# Low_Pass_Filter.net
KiCad netlist of a schematic drawn in Altium Designer
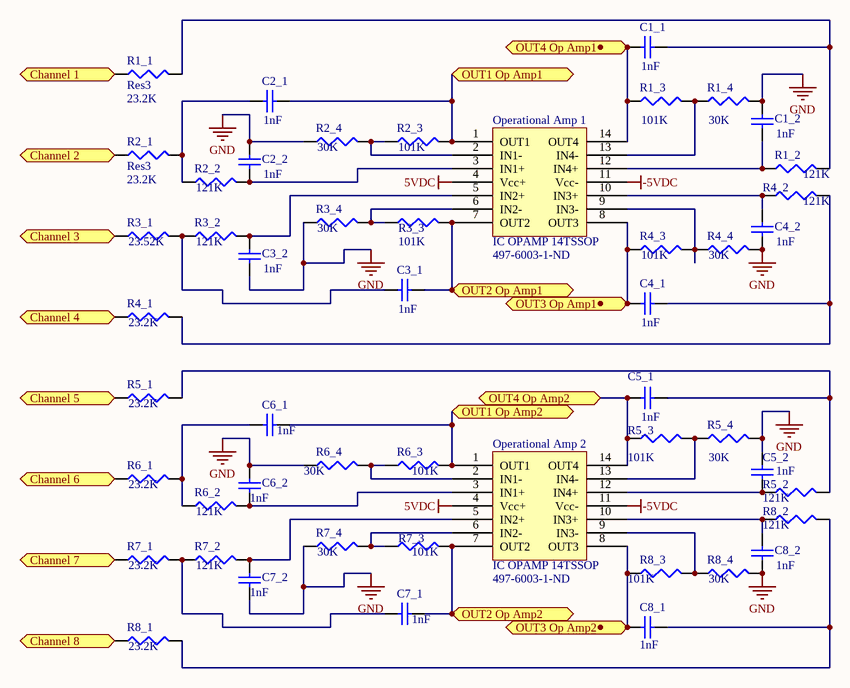
[diagram p0: Low Pass Filter.SchDoc]

(export (version "E")
  (design (tool "Eeschema 10.0.6"))
  (components
    (comp (ref "C1_1")
      (value "1nF")
      (footprint "C1206")
      (description "Capacitor (Semiconductor SIM Model)")
      (fields (field (name "Comment") "Cap Semi") (field (name "PUBLISHER") "Altium Limited"))
      (libsource (lib "Miscellaneous Devices") (part "Cap Semi"))
    )
    (comp (ref "C1_2")
      (value "1nF")
      (footprint "C1206")
      (description "Capacitor (Semiconductor SIM Model)")
      (fields (field (name "Comment") "Cap Semi") (field (name "PUBLISHER") "Altium Limited"))
      (libsource (lib "Miscellaneous Devices") (part "Cap Semi"))
    )
    (comp (ref "C2_1")
      (value "1nF")
      (footprint "C1206")
      (description "Capacitor (Semiconductor SIM Model)")
      (fields (field (name "Comment") "Cap Semi") (field (name "PUBLISHER") "Altium Limited"))
      (libsource (lib "Miscellaneous Devices") (part "Cap Semi"))
    )
    (comp (ref "C2_2")
      (value "1nF")
      (footprint "C1206")
      (description "Capacitor (Semiconductor SIM Model)")
      (fields (field (name "Comment") "Cap Semi") (field (name "PUBLISHER") "Altium Limited"))
      (libsource (lib "Miscellaneous Devices") (part "Cap Semi"))
    )
    (comp (ref "C3_1")
      (value "1nF")
      (footprint "C1206")
      (description "Capacitor (Semiconductor SIM Model)")
      (fields (field (name "Comment") "Cap Semi") (field (name "PUBLISHER") "Altium Limited"))
      (libsource (lib "Miscellaneous Devices") (part "Cap Semi"))
    )
    (comp (ref "C3_2")
      (value "1nF")
      (footprint "C1206")
      (description "Capacitor (Semiconductor SIM Model)")
      (fields (field (name "Comment") "Cap Semi") (field (name "PUBLISHER") "Altium Limited"))
      (libsource (lib "Miscellaneous Devices") (part "Cap Semi"))
    )
    (comp (ref "C4_1")
      (value "1nF")
      (footprint "C1206")
      (description "Capacitor (Semiconductor SIM Model)")
      (fields (field (name "Comment") "Cap Semi") (field (name "PUBLISHER") "Altium Limited"))
      (libsource (lib "Miscellaneous Devices") (part "Cap Semi"))
    )
    (comp (ref "C4_2")
      (value "1nF")
      (footprint "C1206")
      (description "Capacitor (Semiconductor SIM Model)")
      (fields (field (name "Comment") "Cap Semi") (field (name "PUBLISHER") "Altium Limited"))
      (libsource (lib "Miscellaneous Devices") (part "Cap Semi"))
    )
    (comp (ref "C5_1")
      (value "1nF")
      (footprint "C1206")
      (description "Capacitor (Semiconductor SIM Model)")
      (fields (field (name "Comment") "Cap Semi") (field (name "PUBLISHER") "Altium Limited"))
      (libsource (lib "Miscellaneous Devices") (part "Cap Semi"))
    )
    (comp (ref "C5_2")
      (value "1nF")
      (footprint "C1206")
      (description "Capacitor (Semiconductor SIM Model)")
      (fields (field (name "Comment") "Cap Semi") (field (name "PUBLISHER") "Altium Limited"))
      (libsource (lib "Miscellaneous Devices") (part "Cap Semi"))
    )
    (comp (ref "C6_1")
      (value "1nF")
      (footprint "C1206")
      (description "Capacitor (Semiconductor SIM Model)")
      (fields (field (name "Comment") "Cap Semi") (field (name "PUBLISHER") "Altium Limited"))
      (libsource (lib "Miscellaneous Devices") (part "Cap Semi"))
    )
    (comp (ref "C6_2")
      (value "1nF")
      (footprint "C1206")
      (description "Capacitor (Semiconductor SIM Model)")
      (fields (field (name "Comment") "Cap Semi") (field (name "PUBLISHER") "Altium Limited"))
      (libsource (lib "Miscellaneous Devices") (part "Cap Semi"))
    )
    (comp (ref "C7_1")
      (value "1nF")
      (footprint "C1206")
      (description "Capacitor (Semiconductor SIM Model)")
      (fields (field (name "Comment") "Cap Semi") (field (name "PUBLISHER") "Altium Limited"))
      (libsource (lib "Miscellaneous Devices") (part "Cap Semi"))
    )
    (comp (ref "C7_2")
      (value "1nF")
      (footprint "C1206")
      (description "Capacitor (Semiconductor SIM Model)")
      (fields (field (name "Comment") "Cap Semi") (field (name "PUBLISHER") "Altium Limited"))
      (libsource (lib "Miscellaneous Devices") (part "Cap Semi"))
    )
    (comp (ref "C8_1")
      (value "1nF")
      (footprint "C1206")
      (description "Capacitor (Semiconductor SIM Model)")
      (fields (field (name "Comment") "Cap Semi") (field (name "PUBLISHER") "Altium Limited"))
      (libsource (lib "Miscellaneous Devices") (part "Cap Semi"))
    )
    (comp (ref "C8_2")
      (value "1nF")
      (footprint "C1206")
      (description "Capacitor (Semiconductor SIM Model)")
      (fields (field (name "Comment") "Cap Semi") (field (name "PUBLISHER") "Altium Limited"))
      (libsource (lib "Miscellaneous Devices") (part "Cap Semi"))
    )
    (comp (ref "Operational Amp 1")
      (value "IC OPAMP 14TSSOP")
      (footprint "TSV994IPT")
      (fields (field (name "SUPPLIER PART NUMBER 1") "497-6003-1-ND"))
      (libsource (lib "TSV994IPT") (part "Component_1"))
    )
    (comp (ref "Operational Amp 2")
      (value "IC OPAMP 14TSSOP")
      (footprint "TSV994IPT")
      (fields (field (name "SUPPLIER PART NUMBER 1") "497-6003-1-ND"))
      (libsource (lib "TSV994IPT") (part "Component_1"))
    )
    (comp (ref "R1_1")
      (value "Res3")
      (footprint "J1-0603")
      (description "Resistor")
      (fields (field (name "ALTIUM_VALUE") "23.2K") (field (name "PUBLISHER") "Altium Limited"))
      (libsource (lib "Miscellaneous Devices") (part "Res3"))
    )
    (comp (ref "R1_2")
      (value "121K")
      (footprint "J1-0603")
      (description "Resistor")
      (fields (field (name "Comment") "Res3") (field (name "PUBLISHER") "Altium Limited"))
      (libsource (lib "Miscellaneous Devices") (part "Res3"))
    )
    (comp (ref "R1_3")
      (value "101K")
      (footprint "J1-0603")
      (description "Resistor")
      (fields (field (name "Comment") "Res3") (field (name "PUBLISHER") "Altium Limited"))
      (libsource (lib "Miscellaneous Devices") (part "Res3"))
    )
    (comp (ref "R1_4")
      (value "30K")
      (footprint "J1-0603")
      (description "Resistor")
      (fields (field (name "Comment") "Res3") (field (name "PUBLISHER") "Altium Limited"))
      (libsource (lib "Miscellaneous Devices") (part "Res3"))
    )
    (comp (ref "R2_1")
      (value "Res3")
      (footprint "J1-0603")
      (description "Resistor")
      (fields (field (name "ALTIUM_VALUE") "23.2K") (field (name "PUBLISHER") "Altium Limited"))
      (libsource (lib "Miscellaneous Devices") (part "Res3"))
    )
    (comp (ref "R2_2")
      (value "121K")
      (footprint "J1-0603")
      (description "Resistor")
      (fields (field (name "Comment") "Res3") (field (name "PUBLISHER") "Altium Limited"))
      (libsource (lib "Miscellaneous Devices") (part "Res3"))
    )
    (comp (ref "R2_3")
      (value "101K")
      (footprint "J1-0603")
      (description "Resistor")
      (fields (field (name "Comment") "Res3") (field (name "PUBLISHER") "Altium Limited"))
      (libsource (lib "Miscellaneous Devices") (part "Res3"))
    )
    (comp (ref "R2_4")
      (value "30K")
      (footprint "J1-0603")
      (description "Resistor")
      (fields (field (name "Comment") "Res3") (field (name "PUBLISHER") "Altium Limited"))
      (libsource (lib "Miscellaneous Devices") (part "Res3"))
    )
    (comp (ref "R3_1")
      (value "23.52K")
      (footprint "J1-0603")
      (description "Resistor")
      (fields (field (name "Comment") "Res3") (field (name "PUBLISHER") "Altium Limited"))
      (libsource (lib "Miscellaneous Devices") (part "Res3"))
    )
    (comp (ref "R3_2")
      (value "121K")
      (footprint "J1-0603")
      (description "Resistor")
      (fields (field (name "Comment") "Res3") (field (name "PUBLISHER") "Altium Limited"))
      (libsource (lib "Miscellaneous Devices") (part "Res3"))
    )
    (comp (ref "R3_3")
      (value "101K")
      (footprint "J1-0603")
      (description "Resistor")
      (fields (field (name "Comment") "Res3") (field (name "PUBLISHER") "Altium Limited"))
      (libsource (lib "Miscellaneous Devices") (part "Res3"))
    )
    (comp (ref "R3_4")
      (value "30K")
      (footprint "J1-0603")
      (description "Resistor")
      (fields (field (name "Comment") "Res3") (field (name "PUBLISHER") "Altium Limited"))
      (libsource (lib "Miscellaneous Devices") (part "Res3"))
    )
    (comp (ref "R4_1")
      (value "23.2K")
      (footprint "J1-0603")
      (description "Resistor")
      (fields (field (name "Comment") "Res3") (field (name "PUBLISHER") "Altium Limited"))
      (libsource (lib "Miscellaneous Devices") (part "Res3"))
    )
    (comp (ref "R4_2")
      (value "121K")
      (footprint "J1-0603")
      (description "Resistor")
      (fields (field (name "Comment") "Res3") (field (name "PUBLISHER") "Altium Limited"))
      (libsource (lib "Miscellaneous Devices") (part "Res3"))
    )
    (comp (ref "R4_3")
      (value "101K")
      (footprint "J1-0603")
      (description "Resistor")
      (fields (field (name "Comment") "Res3") (field (name "PUBLISHER") "Altium Limited"))
      (libsource (lib "Miscellaneous Devices") (part "Res3"))
    )
    (comp (ref "R4_4")
      (value "30K")
      (footprint "J1-0603")
      (description "Resistor")
      (fields (field (name "Comment") "Res3") (field (name "PUBLISHER") "Altium Limited"))
      (libsource (lib "Miscellaneous Devices") (part "Res3"))
    )
    (comp (ref "R5_1")
      (value "23.2K")
      (footprint "J1-0603")
      (description "Resistor")
      (fields (field (name "Comment") "Res3") (field (name "PUBLISHER") "Altium Limited"))
      (libsource (lib "Miscellaneous Devices") (part "Res3"))
    )
    (comp (ref "R5_2")
      (value "121K")
      (footprint "J1-0603")
      (description "Resistor")
      (fields (field (name "Comment") "Res3") (field (name "PUBLISHER") "Altium Limited"))
      (libsource (lib "Miscellaneous Devices") (part "Res3"))
    )
    (comp (ref "R5_3")
      (value "101K")
      (footprint "J1-0603")
      (description "Resistor")
      (fields (field (name "Comment") "Res3") (field (name "PUBLISHER") "Altium Limited"))
      (libsource (lib "Miscellaneous Devices") (part "Res3"))
    )
    (comp (ref "R5_4")
      (value "30K")
      (footprint "J1-0603")
      (description "Resistor")
      (fields (field (name "Comment") "Res3") (field (name "PUBLISHER") "Altium Limited"))
      (libsource (lib "Miscellaneous Devices") (part "Res3"))
    )
    (comp (ref "R6_1")
      (value "23.2K")
      (footprint "J1-0603")
      (description "Resistor")
      (fields (field (name "Comment") "Res3") (field (name "PUBLISHER") "Altium Limited"))
      (libsource (lib "Miscellaneous Devices") (part "Res3"))
    )
    (comp (ref "R6_2")
      (value "121K")
      (footprint "J1-0603")
      (description "Resistor")
      (fields (field (name "Comment") "Res3") (field (name "PUBLISHER") "Altium Limited"))
      (libsource (lib "Miscellaneous Devices") (part "Res3"))
    )
    (comp (ref "R6_3")
      (value "101K")
      (footprint "J1-0603")
      (description "Resistor")
      (fields (field (name "Comment") "Res3") (field (name "PUBLISHER") "Altium Limited"))
      (libsource (lib "Miscellaneous Devices") (part "Res3"))
    )
    (comp (ref "R6_4")
      (value "30K")
      (footprint "J1-0603")
      (description "Resistor")
      (fields (field (name "Comment") "Res3") (field (name "PUBLISHER") "Altium Limited"))
      (libsource (lib "Miscellaneous Devices") (part "Res3"))
    )
    (comp (ref "R7_1")
      (value "23.2K")
      (footprint "J1-0603")
      (description "Resistor")
      (fields (field (name "Comment") "Res3") (field (name "PUBLISHER") "Altium Limited"))
      (libsource (lib "Miscellaneous Devices") (part "Res3"))
    )
    (comp (ref "R7_2")
      (value "121K")
      (footprint "J1-0603")
      (description "Resistor")
      (fields (field (name "Comment") "Res3") (field (name "PUBLISHER") "Altium Limited"))
      (libsource (lib "Miscellaneous Devices") (part "Res3"))
    )
    (comp (ref "R7_3")
      (value "101K")
      (footprint "J1-0603")
      (description "Resistor")
      (fields (field (name "Comment") "Res3") (field (name "PUBLISHER") "Altium Limited"))
      (libsource (lib "Miscellaneous Devices") (part "Res3"))
    )
    (comp (ref "R7_4")
      (value "30K")
      (footprint "J1-0603")
      (description "Resistor")
      (fields (field (name "Comment") "Res3") (field (name "PUBLISHER") "Altium Limited"))
      (libsource (lib "Miscellaneous Devices") (part "Res3"))
    )
    (comp (ref "R8_1")
      (value "23.2K")
      (footprint "J1-0603")
      (description "Resistor")
      (fields (field (name "Comment") "Res3") (field (name "PUBLISHER") "Altium Limited"))
      (libsource (lib "Miscellaneous Devices") (part "Res3"))
    )
    (comp (ref "R8_2")
      (value "121K")
      (footprint "J1-0603")
      (description "Resistor")
      (fields (field (name "Comment") "Res3") (field (name "PUBLISHER") "Altium Limited"))
      (libsource (lib "Miscellaneous Devices") (part "Res3"))
    )
    (comp (ref "R8_3")
      (value "101K")
      (footprint "J1-0603")
      (description "Resistor")
      (fields (field (name "Comment") "Res3") (field (name "PUBLISHER") "Altium Limited"))
      (libsource (lib "Miscellaneous Devices") (part "Res3"))
    )
    (comp (ref "R8_4")
      (value "30K")
      (footprint "J1-0603")
      (description "Resistor")
      (fields (field (name "Comment") "Res3") (field (name "PUBLISHER") "Altium Limited"))
      (libsource (lib "Miscellaneous Devices") (part "Res3"))
    )
  )
  (nets
    (net (code "1") (name "-5VDC") (class "Default")
      (node (ref "Operational Amp 1") (pin "11") (pinfunction "Vcc-_11") (pintype "passive"))
      (node (ref "Operational Amp 2") (pin "11") (pinfunction "Vcc-_11") (pintype "passive"))
    )
    (net (code "2") (name "/Channel 1") (class "Default")
      (node (ref "R1_1") (pin "1") (pinfunction "1_1") (pintype "passive"))
    )
    (net (code "3") (name "/Channel 2") (class "Default")
      (node (ref "R2_1") (pin "1") (pinfunction "1_1") (pintype "passive"))
    )
    (net (code "4") (name "/Channel 3") (class "Default")
      (node (ref "R3_1") (pin "1") (pinfunction "1_1") (pintype "passive"))
    )
    (net (code "5") (name "/Channel 4") (class "Default")
      (node (ref "R4_1") (pin "1") (pinfunction "1_1") (pintype "passive"))
    )
    (net (code "6") (name "/Channel 5") (class "Default")
      (node (ref "R5_1") (pin "1") (pinfunction "1_1") (pintype "passive"))
    )
    (net (code "7") (name "/Channel 6") (class "Default")
      (node (ref "R6_1") (pin "1") (pinfunction "1_1") (pintype "passive"))
    )
    (net (code "8") (name "/Channel 7") (class "Default")
      (node (ref "R7_1") (pin "1") (pinfunction "1_1") (pintype "passive"))
    )
    (net (code "9") (name "/Channel 8") (class "Default")
      (node (ref "R8_1") (pin "1") (pinfunction "1_1") (pintype "passive"))
    )
    (net (code "10") (name "/OUT1 Op Amp1") (class "Default")
      (node (ref "C2_1") (pin "2") (pinfunction "2_2") (pintype "passive"))
      (node (ref "Operational Amp 1") (pin "1") (pinfunction "OUT1_1") (pintype "passive"))
      (node (ref "R2_3") (pin "2") (pinfunction "2_2") (pintype "passive"))
    )
    (net (code "11") (name "/OUT1 Op Amp2") (class "Default")
      (node (ref "C6_1") (pin "2") (pinfunction "2_2") (pintype "passive"))
      (node (ref "Operational Amp 2") (pin "1") (pinfunction "OUT1_1") (pintype "passive"))
      (node (ref "R6_3") (pin "2") (pinfunction "2_2") (pintype "passive"))
    )
    (net (code "12") (name "/OUT2 Op Amp1") (class "Default")
      (node (ref "C3_1") (pin "2") (pinfunction "2_2") (pintype "passive"))
      (node (ref "Operational Amp 1") (pin "7") (pinfunction "OUT2_7") (pintype "passive"))
      (node (ref "R3_3") (pin "2") (pinfunction "2_2") (pintype "passive"))
    )
    (net (code "13") (name "/OUT2 Op Amp2") (class "Default")
      (node (ref "C7_1") (pin "2") (pinfunction "2_2") (pintype "passive"))
      (node (ref "Operational Amp 2") (pin "7") (pinfunction "OUT2_7") (pintype "passive"))
      (node (ref "R7_3") (pin "2") (pinfunction "2_2") (pintype "passive"))
    )
    (net (code "14") (name "/OUT3 Op Amp1") (class "Default")
      (node (ref "C4_1") (pin "1") (pinfunction "1_1") (pintype "passive"))
      (node (ref "Operational Amp 1") (pin "8") (pinfunction "OUT3_8") (pintype "passive"))
      (node (ref "R4_3") (pin "1") (pinfunction "1_1") (pintype "passive"))
    )
    (net (code "15") (name "/OUT3 Op Amp2") (class "Default")
      (node (ref "C8_1") (pin "2") (pinfunction "2_2") (pintype "passive"))
      (node (ref "Operational Amp 2") (pin "8") (pinfunction "OUT3_8") (pintype "passive"))
      (node (ref "R8_3") (pin "1") (pinfunction "1_1") (pintype "passive"))
    )
    (net (code "16") (name "/OUT4 Op Amp1") (class "Default")
      (node (ref "C1_1") (pin "1") (pinfunction "1_1") (pintype "passive"))
      (node (ref "Operational Amp 1") (pin "14") (pinfunction "OUT4_14") (pintype "passive"))
      (node (ref "R1_3") (pin "1") (pinfunction "1_1") (pintype "passive"))
    )
    (net (code "17") (name "/OUT4 Op Amp2") (class "Default")
      (node (ref "C5_1") (pin "1") (pinfunction "1_1") (pintype "passive"))
      (node (ref "Operational Amp 2") (pin "14") (pinfunction "OUT4_14") (pintype "passive"))
      (node (ref "R5_3") (pin "1") (pinfunction "1_1") (pintype "passive"))
    )
    (net (code "18") (name "5VDC") (class "Default")
      (node (ref "Operational Amp 1") (pin "4") (pinfunction "Vcc+_4") (pintype "passive"))
      (node (ref "Operational Amp 2") (pin "4") (pinfunction "Vcc+_4") (pintype "passive"))
    )
    (net (code "19") (name "GND") (class "Default")
      (node (ref "C1_2") (pin "1") (pinfunction "1_1") (pintype "passive"))
      (node (ref "C2_2") (pin "2") (pinfunction "2_2") (pintype "passive"))
      (node (ref "C3_2") (pin "1") (pinfunction "1_1") (pintype "passive"))
      (node (ref "C4_2") (pin "1") (pinfunction "1_1") (pintype "passive"))
      (node (ref "C5_2") (pin "2") (pinfunction "2_2") (pintype "passive"))
      (node (ref "C6_2") (pin "2") (pinfunction "2_2") (pintype "passive"))
      (node (ref "C7_2") (pin "1") (pinfunction "1_1") (pintype "passive"))
      (node (ref "C8_2") (pin "1") (pinfunction "1_1") (pintype "passive"))
      (node (ref "R1_4") (pin "2") (pinfunction "2_2") (pintype "passive"))
      (node (ref "R2_4") (pin "1") (pinfunction "1_1") (pintype "passive"))
      (node (ref "R3_4") (pin "1") (pinfunction "1_1") (pintype "passive"))
      (node (ref "R4_4") (pin "2") (pinfunction "2_2") (pintype "passive"))
      (node (ref "R5_4") (pin "2") (pinfunction "2_2") (pintype "passive"))
      (node (ref "R6_4") (pin "1") (pinfunction "1_1") (pintype "passive"))
      (node (ref "R7_4") (pin "1") (pinfunction "1_1") (pintype "passive"))
      (node (ref "R8_4") (pin "2") (pinfunction "2_2") (pintype "passive"))
    )
    (net (code "20") (name "Net-(C1_1-Pad2)") (class "Default")
      (node (ref "C1_1") (pin "2") (pinfunction "2_2") (pintype "passive"))
      (node (ref "R1_1") (pin "2") (pinfunction "2_2") (pintype "passive"))
      (node (ref "R1_2") (pin "2") (pinfunction "2_2") (pintype "passive"))
    )
    (net (code "21") (name "Net-(C2_1-Pad1)") (class "Default")
      (node (ref "C2_1") (pin "1") (pinfunction "1_1") (pintype "passive"))
      (node (ref "R2_1") (pin "2") (pinfunction "2_2") (pintype "passive"))
      (node (ref "R2_2") (pin "1") (pinfunction "1_1") (pintype "passive"))
    )
    (net (code "22") (name "Net-(C3_1-Pad1)") (class "Default")
      (node (ref "C3_1") (pin "1") (pinfunction "1_1") (pintype "passive"))
      (node (ref "R3_1") (pin "2") (pinfunction "2_2") (pintype "passive"))
      (node (ref "R3_2") (pin "1") (pinfunction "1_1") (pintype "passive"))
    )
    (net (code "23") (name "Net-(C4_1-Pad2)") (class "Default")
      (node (ref "C4_1") (pin "2") (pinfunction "2_2") (pintype "passive"))
      (node (ref "R4_1") (pin "2") (pinfunction "2_2") (pintype "passive"))
      (node (ref "R4_2") (pin "2") (pinfunction "2_2") (pintype "passive"))
    )
    (net (code "24") (name "Net-(C5_1-Pad2)") (class "Default")
      (node (ref "C5_1") (pin "2") (pinfunction "2_2") (pintype "passive"))
      (node (ref "R5_1") (pin "2") (pinfunction "2_2") (pintype "passive"))
      (node (ref "R5_2") (pin "2") (pinfunction "2_2") (pintype "passive"))
    )
    (net (code "25") (name "Net-(C6_1-Pad1)") (class "Default")
      (node (ref "C6_1") (pin "1") (pinfunction "1_1") (pintype "passive"))
      (node (ref "R6_1") (pin "2") (pinfunction "2_2") (pintype "passive"))
      (node (ref "R6_2") (pin "1") (pinfunction "1_1") (pintype "passive"))
    )
    (net (code "26") (name "Net-(C7_1-Pad1)") (class "Default")
      (node (ref "C7_1") (pin "1") (pinfunction "1_1") (pintype "passive"))
      (node (ref "R7_1") (pin "2") (pinfunction "2_2") (pintype "passive"))
      (node (ref "R7_2") (pin "1") (pinfunction "1_1") (pintype "passive"))
    )
    (net (code "27") (name "Net-(C8_1-Pad1)") (class "Default")
      (node (ref "C8_1") (pin "1") (pinfunction "1_1") (pintype "passive"))
      (node (ref "R8_1") (pin "2") (pinfunction "2_2") (pintype "passive"))
      (node (ref "R8_2") (pin "2") (pinfunction "2_2") (pintype "passive"))
    )
    (net (code "28") (name "Net-(Operational Amp 1-IN1+)") (class "Default")
      (node (ref "C2_2") (pin "1") (pinfunction "1_1") (pintype "passive"))
      (node (ref "Operational Amp 1") (pin "3") (pinfunction "IN1+_3") (pintype "passive"))
      (node (ref "R2_2") (pin "2") (pinfunction "2_2") (pintype "passive"))
    )
    (net (code "29") (name "Net-(Operational Amp 1-IN1-)") (class "Default")
      (node (ref "Operational Amp 1") (pin "2") (pinfunction "IN1-_2") (pintype "passive"))
      (node (ref "R2_3") (pin "1") (pinfunction "1_1") (pintype "passive"))
      (node (ref "R2_4") (pin "2") (pinfunction "2_2") (pintype "passive"))
    )
    (net (code "30") (name "Net-(Operational Amp 1-IN2+)") (class "Default")
      (node (ref "C3_2") (pin "2") (pinfunction "2_2") (pintype "passive"))
      (node (ref "Operational Amp 1") (pin "5") (pinfunction "IN2+_5") (pintype "passive"))
      (node (ref "R3_2") (pin "2") (pinfunction "2_2") (pintype "passive"))
    )
    (net (code "31") (name "Net-(Operational Amp 1-IN2-)") (class "Default")
      (node (ref "Operational Amp 1") (pin "6") (pinfunction "IN2-_6") (pintype "passive"))
      (node (ref "R3_3") (pin "1") (pinfunction "1_1") (pintype "passive"))
      (node (ref "R3_4") (pin "2") (pinfunction "2_2") (pintype "passive"))
    )
    (net (code "32") (name "Net-(Operational Amp 1-IN3+)") (class "Default")
      (node (ref "C4_2") (pin "2") (pinfunction "2_2") (pintype "passive"))
      (node (ref "Operational Amp 1") (pin "10") (pinfunction "IN3+_10") (pintype "passive"))
      (node (ref "R4_2") (pin "1") (pinfunction "1_1") (pintype "passive"))
    )
    (net (code "33") (name "Net-(Operational Amp 1-IN3-)") (class "Default")
      (node (ref "Operational Amp 1") (pin "9") (pinfunction "IN3-_9") (pintype "passive"))
      (node (ref "R4_3") (pin "2") (pinfunction "2_2") (pintype "passive"))
      (node (ref "R4_4") (pin "1") (pinfunction "1_1") (pintype "passive"))
    )
    (net (code "34") (name "Net-(Operational Amp 1-IN4+)") (class "Default")
      (node (ref "C1_2") (pin "2") (pinfunction "2_2") (pintype "passive"))
      (node (ref "Operational Amp 1") (pin "12") (pinfunction "IN4+_12") (pintype "passive"))
      (node (ref "R1_2") (pin "1") (pinfunction "1_1") (pintype "passive"))
    )
    (net (code "35") (name "Net-(Operational Amp 1-IN4-)") (class "Default")
      (node (ref "Operational Amp 1") (pin "13") (pinfunction "IN4-_13") (pintype "passive"))
      (node (ref "R1_3") (pin "2") (pinfunction "2_2") (pintype "passive"))
      (node (ref "R1_4") (pin "1") (pinfunction "1_1") (pintype "passive"))
    )
    (net (code "36") (name "Net-(Operational Amp 2-IN1+)") (class "Default")
      (node (ref "C6_2") (pin "1") (pinfunction "1_1") (pintype "passive"))
      (node (ref "Operational Amp 2") (pin "3") (pinfunction "IN1+_3") (pintype "passive"))
      (node (ref "R6_2") (pin "2") (pinfunction "2_2") (pintype "passive"))
    )
    (net (code "37") (name "Net-(Operational Amp 2-IN1-)") (class "Default")
      (node (ref "Operational Amp 2") (pin "2") (pinfunction "IN1-_2") (pintype "passive"))
      (node (ref "R6_3") (pin "1") (pinfunction "1_1") (pintype "passive"))
      (node (ref "R6_4") (pin "2") (pinfunction "2_2") (pintype "passive"))
    )
    (net (code "38") (name "Net-(Operational Amp 2-IN2+)") (class "Default")
      (node (ref "C7_2") (pin "2") (pinfunction "2_2") (pintype "passive"))
      (node (ref "Operational Amp 2") (pin "5") (pinfunction "IN2+_5") (pintype "passive"))
      (node (ref "R7_2") (pin "2") (pinfunction "2_2") (pintype "passive"))
    )
    (net (code "39") (name "Net-(Operational Amp 2-IN2-)") (class "Default")
      (node (ref "Operational Amp 2") (pin "6") (pinfunction "IN2-_6") (pintype "passive"))
      (node (ref "R7_3") (pin "1") (pinfunction "1_1") (pintype "passive"))
      (node (ref "R7_4") (pin "2") (pinfunction "2_2") (pintype "passive"))
    )
    (net (code "40") (name "Net-(Operational Amp 2-IN3+)") (class "Default")
      (node (ref "C8_2") (pin "2") (pinfunction "2_2") (pintype "passive"))
      (node (ref "Operational Amp 2") (pin "10") (pinfunction "IN3+_10") (pintype "passive"))
      (node (ref "R8_2") (pin "1") (pinfunction "1_1") (pintype "passive"))
    )
    (net (code "41") (name "Net-(Operational Amp 2-IN3-)") (class "Default")
      (node (ref "Operational Amp 2") (pin "9") (pinfunction "IN3-_9") (pintype "passive"))
      (node (ref "R8_3") (pin "2") (pinfunction "2_2") (pintype "passive"))
      (node (ref "R8_4") (pin "1") (pinfunction "1_1") (pintype "passive"))
    )
    (net (code "42") (name "Net-(Operational Amp 2-IN4+)") (class "Default")
      (node (ref "C5_2") (pin "1") (pinfunction "1_1") (pintype "passive"))
      (node (ref "Operational Amp 2") (pin "12") (pinfunction "IN4+_12") (pintype "passive"))
      (node (ref "R5_2") (pin "1") (pinfunction "1_1") (pintype "passive"))
    )
    (net (code "43") (name "Net-(Operational Amp 2-IN4-)") (class "Default")
      (node (ref "Operational Amp 2") (pin "13") (pinfunction "IN4-_13") (pintype "passive"))
      (node (ref "R5_3") (pin "2") (pinfunction "2_2") (pintype "passive"))
      (node (ref "R5_4") (pin "1") (pinfunction "1_1") (pintype "passive"))
    )
  )
)
